# departure_board_display.net
KiCad netlist of a schematic drawn in EasyEDA Pro
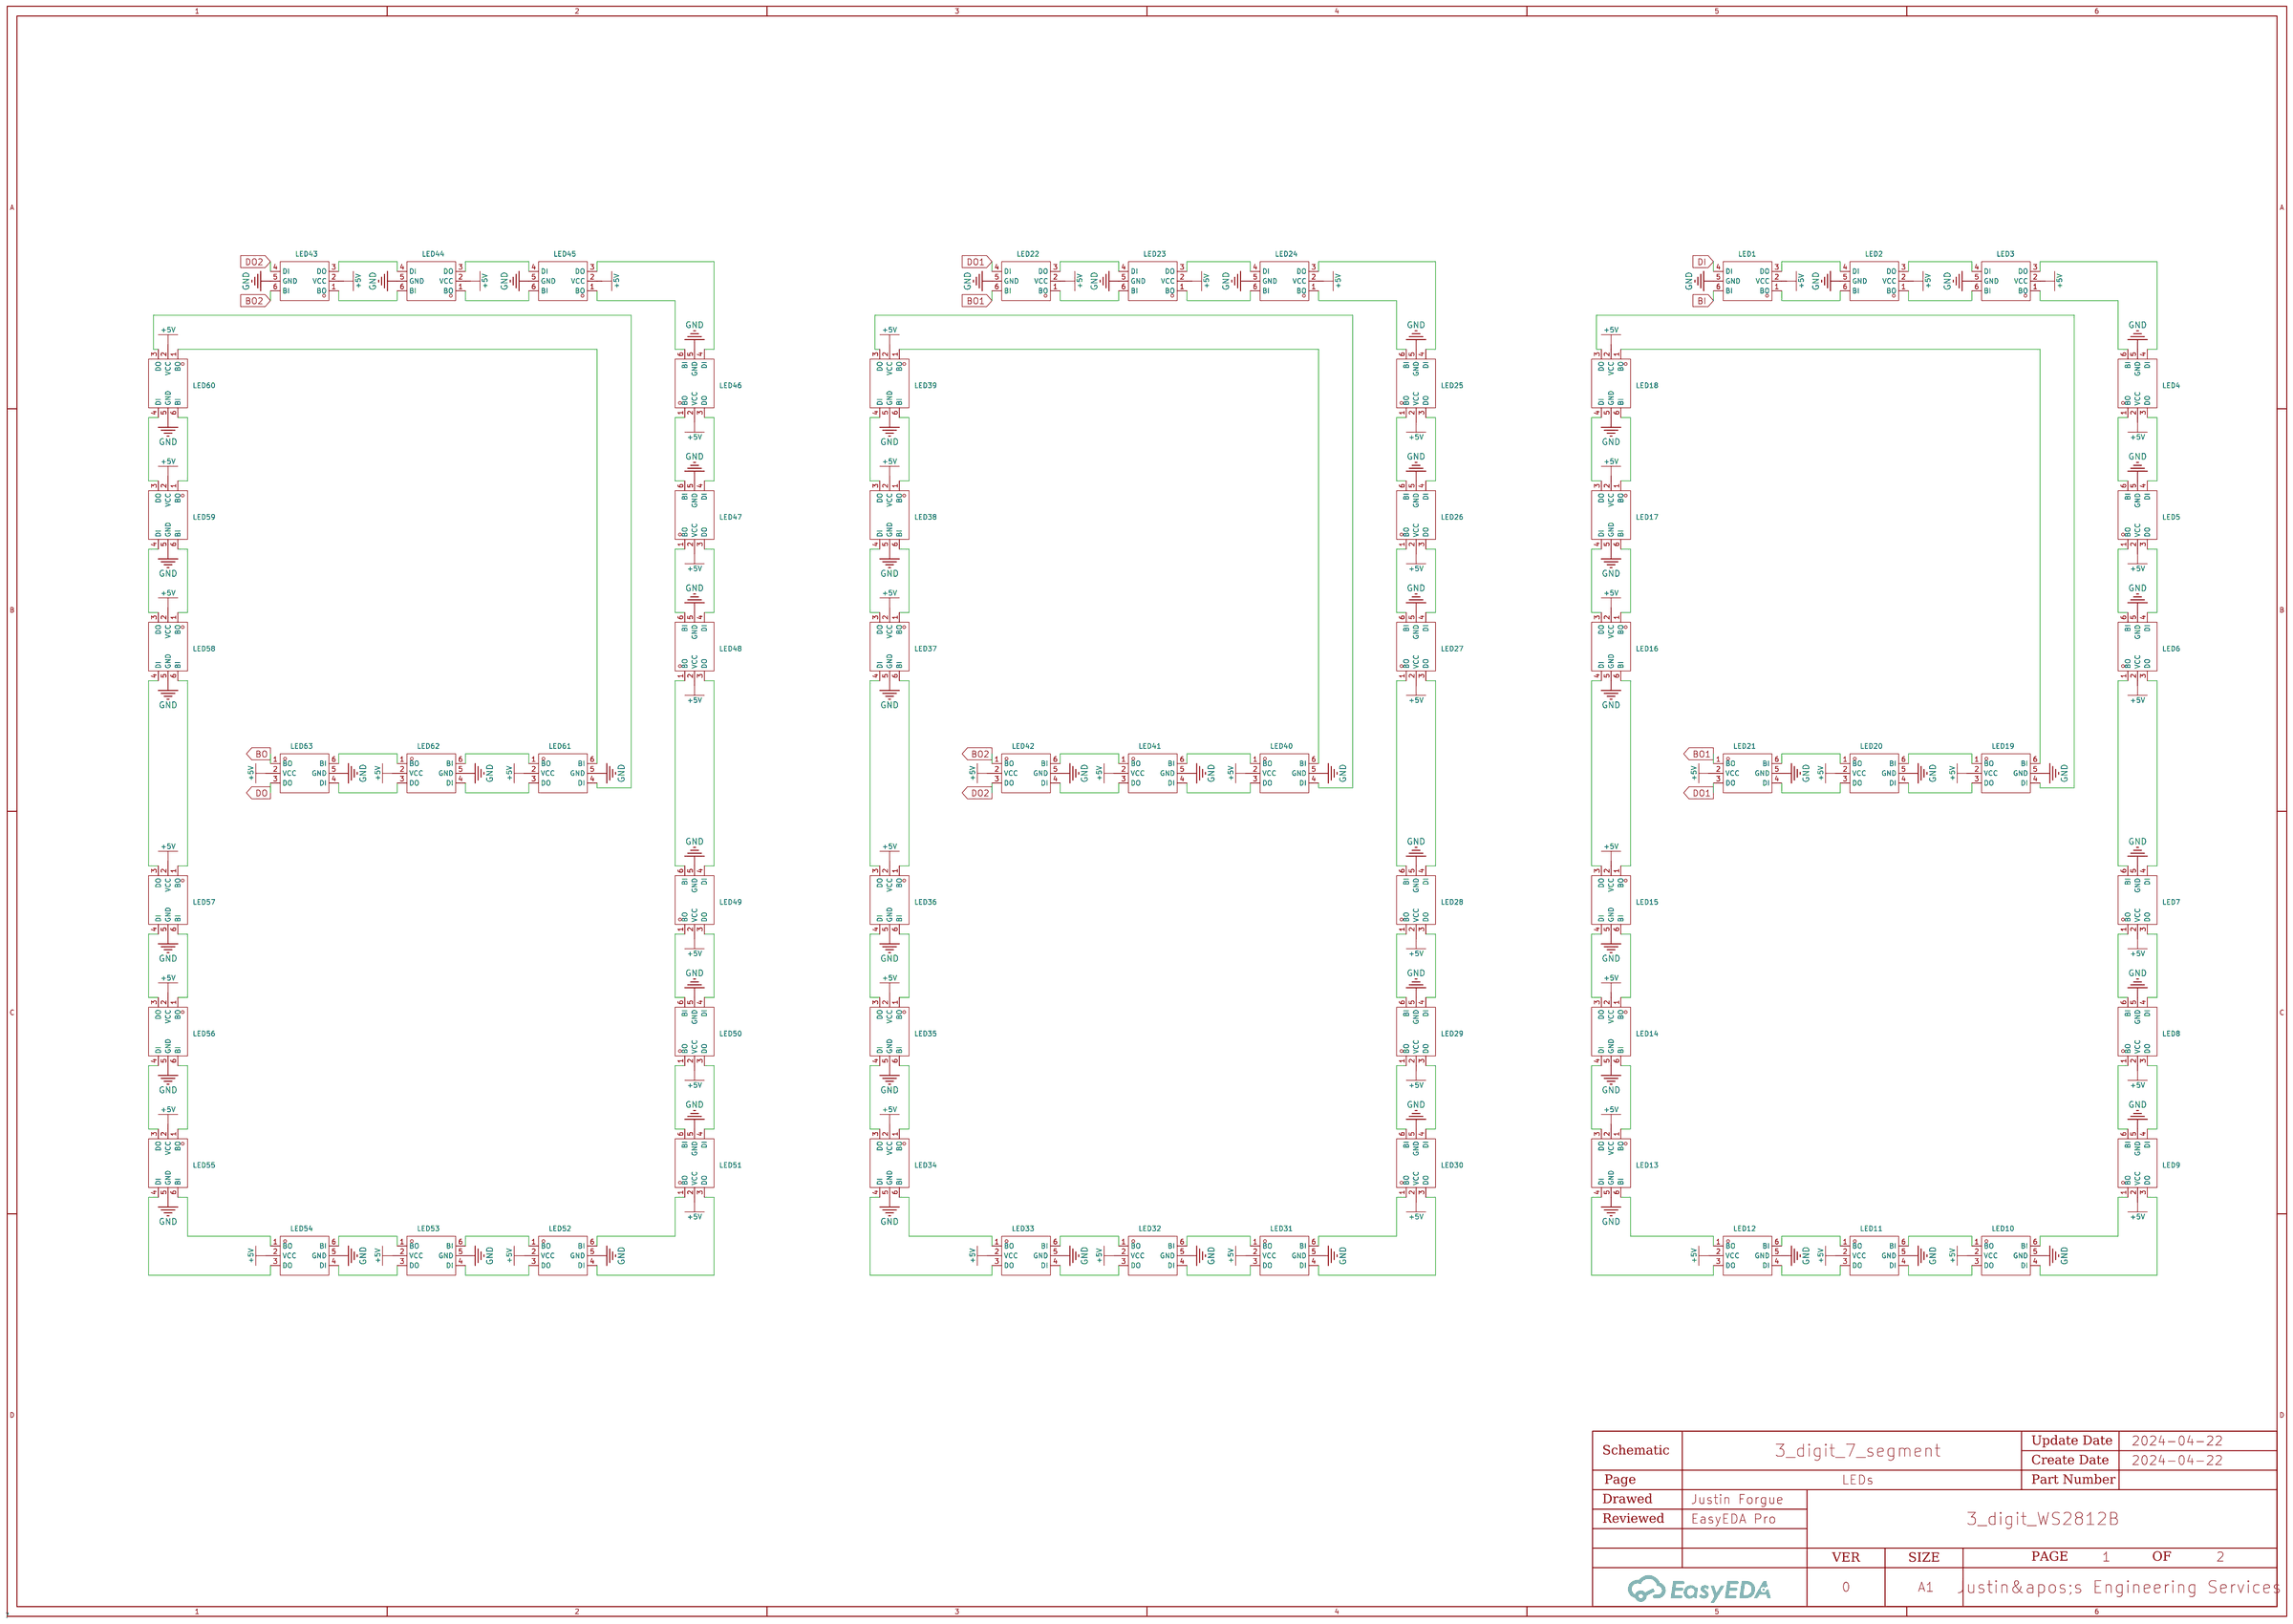
[diagram p0: LEDs]
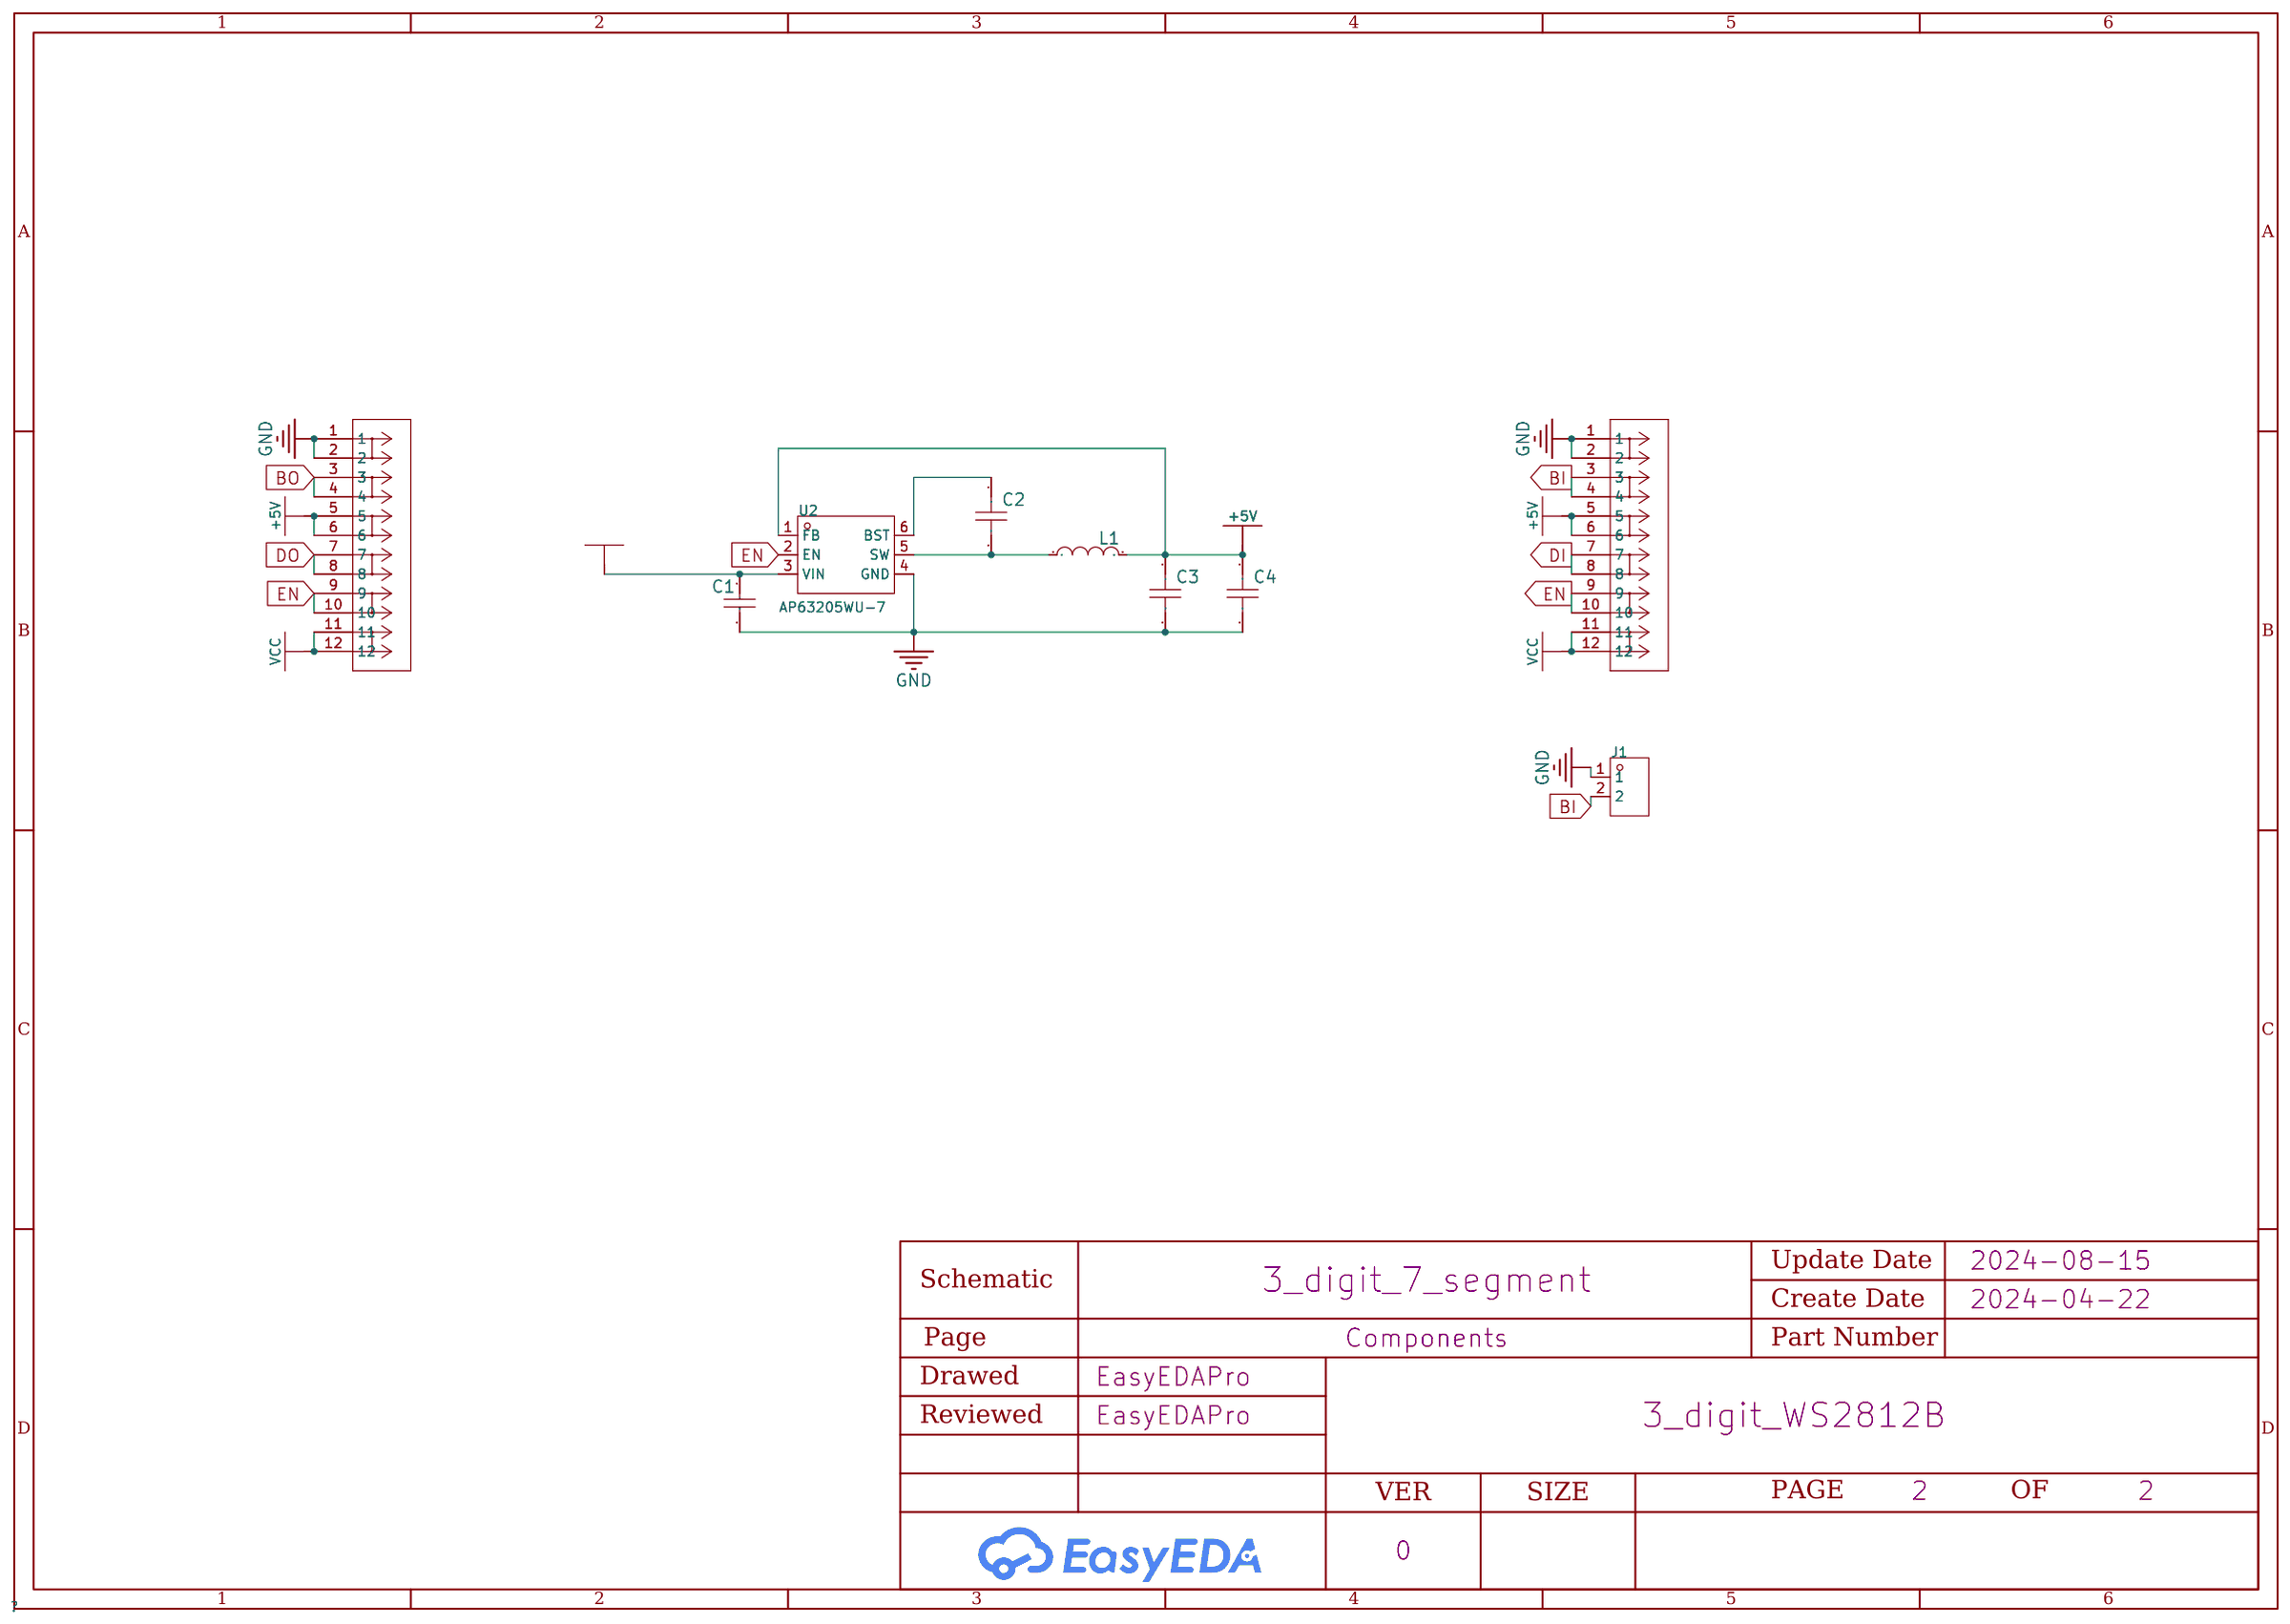
[diagram p1: Components]

(export (version "E")
  (design (tool "Eeschema 10.0.6"))
  (components
    (comp (ref "LED1")
      (value "WS2813B-V5")
      (footprint "easyedapro:LED-SMD_6P-L5.0-W5.0-TL")
      (fields (field (name "Manufacturer") "worldsemi"))
      (libsource (lib "easyedapro") (part "WS2813B-V5"))
    )
    (comp (ref "LED2")
      (value "WS2813B-V5")
      (footprint "easyedapro:LED-SMD_6P-L5.0-W5.0-TL")
      (fields (field (name "Manufacturer") "worldsemi"))
      (libsource (lib "easyedapro") (part "WS2813B-V5"))
    )
    (comp (ref "LED3")
      (value "WS2813B-V5")
      (footprint "easyedapro:LED-SMD_6P-L5.0-W5.0-TL")
      (fields (field (name "Manufacturer") "worldsemi"))
      (libsource (lib "easyedapro") (part "WS2813B-V5"))
    )
    (comp (ref "LED4")
      (value "WS2813B-V5")
      (footprint "easyedapro:LED-SMD_6P-L5.0-W5.0-TL")
      (fields (field (name "Manufacturer") "worldsemi"))
      (libsource (lib "easyedapro") (part "WS2813B-V5"))
    )
    (comp (ref "LED5")
      (value "WS2813B-V5")
      (footprint "easyedapro:LED-SMD_6P-L5.0-W5.0-TL")
      (fields (field (name "Manufacturer") "worldsemi"))
      (libsource (lib "easyedapro") (part "WS2813B-V5"))
    )
    (comp (ref "LED6")
      (value "WS2813B-V5")
      (footprint "easyedapro:LED-SMD_6P-L5.0-W5.0-TL")
      (fields (field (name "Manufacturer") "worldsemi"))
      (libsource (lib "easyedapro") (part "WS2813B-V5"))
    )
    (comp (ref "LED7")
      (value "WS2813B-V5")
      (footprint "easyedapro:LED-SMD_6P-L5.0-W5.0-TL")
      (fields (field (name "Manufacturer") "worldsemi"))
      (libsource (lib "easyedapro") (part "WS2813B-V5"))
    )
    (comp (ref "LED8")
      (value "WS2813B-V5")
      (footprint "easyedapro:LED-SMD_6P-L5.0-W5.0-TL")
      (fields (field (name "Manufacturer") "worldsemi"))
      (libsource (lib "easyedapro") (part "WS2813B-V5"))
    )
    (comp (ref "LED9")
      (value "WS2813B-V5")
      (footprint "easyedapro:LED-SMD_6P-L5.0-W5.0-TL")
      (fields (field (name "Manufacturer") "worldsemi"))
      (libsource (lib "easyedapro") (part "WS2813B-V5"))
    )
    (comp (ref "LED10")
      (value "WS2813B-V5")
      (footprint "easyedapro:LED-SMD_6P-L5.0-W5.0-TL")
      (fields (field (name "Manufacturer") "worldsemi"))
      (libsource (lib "easyedapro") (part "WS2813B-V5"))
    )
    (comp (ref "LED11")
      (value "WS2813B-V5")
      (footprint "easyedapro:LED-SMD_6P-L5.0-W5.0-TL")
      (fields (field (name "Manufacturer") "worldsemi"))
      (libsource (lib "easyedapro") (part "WS2813B-V5"))
    )
    (comp (ref "LED12")
      (value "WS2813B-V5")
      (footprint "easyedapro:LED-SMD_6P-L5.0-W5.0-TL")
      (fields (field (name "Manufacturer") "worldsemi"))
      (libsource (lib "easyedapro") (part "WS2813B-V5"))
    )
    (comp (ref "LED13")
      (value "WS2813B-V5")
      (footprint "easyedapro:LED-SMD_6P-L5.0-W5.0-TL")
      (fields (field (name "Manufacturer") "worldsemi"))
      (libsource (lib "easyedapro") (part "WS2813B-V5"))
    )
    (comp (ref "LED14")
      (value "WS2813B-V5")
      (footprint "easyedapro:LED-SMD_6P-L5.0-W5.0-TL")
      (fields (field (name "Manufacturer") "worldsemi"))
      (libsource (lib "easyedapro") (part "WS2813B-V5"))
    )
    (comp (ref "LED15")
      (value "WS2813B-V5")
      (footprint "easyedapro:LED-SMD_6P-L5.0-W5.0-TL")
      (fields (field (name "Manufacturer") "worldsemi"))
      (libsource (lib "easyedapro") (part "WS2813B-V5"))
    )
    (comp (ref "LED16")
      (value "WS2813B-V5")
      (footprint "easyedapro:LED-SMD_6P-L5.0-W5.0-TL")
      (fields (field (name "Manufacturer") "worldsemi"))
      (libsource (lib "easyedapro") (part "WS2813B-V5"))
    )
    (comp (ref "LED17")
      (value "WS2813B-V5")
      (footprint "easyedapro:LED-SMD_6P-L5.0-W5.0-TL")
      (fields (field (name "Manufacturer") "worldsemi"))
      (libsource (lib "easyedapro") (part "WS2813B-V5"))
    )
    (comp (ref "LED18")
      (value "WS2813B-V5")
      (footprint "easyedapro:LED-SMD_6P-L5.0-W5.0-TL")
      (fields (field (name "Manufacturer") "worldsemi"))
      (libsource (lib "easyedapro") (part "WS2813B-V5"))
    )
    (comp (ref "LED19")
      (value "WS2813B-V5")
      (footprint "easyedapro:LED-SMD_6P-L5.0-W5.0-TL")
      (fields (field (name "Manufacturer") "worldsemi"))
      (libsource (lib "easyedapro") (part "WS2813B-V5"))
    )
    (comp (ref "LED20")
      (value "WS2813B-V5")
      (footprint "easyedapro:LED-SMD_6P-L5.0-W5.0-TL")
      (fields (field (name "Manufacturer") "worldsemi"))
      (libsource (lib "easyedapro") (part "WS2813B-V5"))
    )
    (comp (ref "LED21")
      (value "WS2813B-V5")
      (footprint "easyedapro:LED-SMD_6P-L5.0-W5.0-TL")
      (fields (field (name "Manufacturer") "worldsemi"))
      (libsource (lib "easyedapro") (part "WS2813B-V5"))
    )
    (comp (ref "LED22")
      (value "WS2813B-V5")
      (footprint "easyedapro:LED-SMD_6P-L5.0-W5.0-TL")
      (fields (field (name "Manufacturer") "worldsemi"))
      (libsource (lib "easyedapro") (part "WS2813B-V5"))
    )
    (comp (ref "LED23")
      (value "WS2813B-V5")
      (footprint "easyedapro:LED-SMD_6P-L5.0-W5.0-TL")
      (fields (field (name "Manufacturer") "worldsemi"))
      (libsource (lib "easyedapro") (part "WS2813B-V5"))
    )
    (comp (ref "LED24")
      (value "WS2813B-V5")
      (footprint "easyedapro:LED-SMD_6P-L5.0-W5.0-TL")
      (fields (field (name "Manufacturer") "worldsemi"))
      (libsource (lib "easyedapro") (part "WS2813B-V5"))
    )
    (comp (ref "LED25")
      (value "WS2813B-V5")
      (footprint "easyedapro:LED-SMD_6P-L5.0-W5.0-TL")
      (fields (field (name "Manufacturer") "worldsemi"))
      (libsource (lib "easyedapro") (part "WS2813B-V5"))
    )
    (comp (ref "LED26")
      (value "WS2813B-V5")
      (footprint "easyedapro:LED-SMD_6P-L5.0-W5.0-TL")
      (fields (field (name "Manufacturer") "worldsemi"))
      (libsource (lib "easyedapro") (part "WS2813B-V5"))
    )
    (comp (ref "LED27")
      (value "WS2813B-V5")
      (footprint "easyedapro:LED-SMD_6P-L5.0-W5.0-TL")
      (fields (field (name "Manufacturer") "worldsemi"))
      (libsource (lib "easyedapro") (part "WS2813B-V5"))
    )
    (comp (ref "LED28")
      (value "WS2813B-V5")
      (footprint "easyedapro:LED-SMD_6P-L5.0-W5.0-TL")
      (fields (field (name "Manufacturer") "worldsemi"))
      (libsource (lib "easyedapro") (part "WS2813B-V5"))
    )
    (comp (ref "LED29")
      (value "WS2813B-V5")
      (footprint "easyedapro:LED-SMD_6P-L5.0-W5.0-TL")
      (fields (field (name "Manufacturer") "worldsemi"))
      (libsource (lib "easyedapro") (part "WS2813B-V5"))
    )
    (comp (ref "LED30")
      (value "WS2813B-V5")
      (footprint "easyedapro:LED-SMD_6P-L5.0-W5.0-TL")
      (fields (field (name "Manufacturer") "worldsemi"))
      (libsource (lib "easyedapro") (part "WS2813B-V5"))
    )
    (comp (ref "LED31")
      (value "WS2813B-V5")
      (footprint "easyedapro:LED-SMD_6P-L5.0-W5.0-TL")
      (fields (field (name "Manufacturer") "worldsemi"))
      (libsource (lib "easyedapro") (part "WS2813B-V5"))
    )
    (comp (ref "LED32")
      (value "WS2813B-V5")
      (footprint "easyedapro:LED-SMD_6P-L5.0-W5.0-TL")
      (fields (field (name "Manufacturer") "worldsemi"))
      (libsource (lib "easyedapro") (part "WS2813B-V5"))
    )
    (comp (ref "LED33")
      (value "WS2813B-V5")
      (footprint "easyedapro:LED-SMD_6P-L5.0-W5.0-TL")
      (fields (field (name "Manufacturer") "worldsemi"))
      (libsource (lib "easyedapro") (part "WS2813B-V5"))
    )
    (comp (ref "LED34")
      (value "WS2813B-V5")
      (footprint "easyedapro:LED-SMD_6P-L5.0-W5.0-TL")
      (fields (field (name "Manufacturer") "worldsemi"))
      (libsource (lib "easyedapro") (part "WS2813B-V5"))
    )
    (comp (ref "LED35")
      (value "WS2813B-V5")
      (footprint "easyedapro:LED-SMD_6P-L5.0-W5.0-TL")
      (fields (field (name "Manufacturer") "worldsemi"))
      (libsource (lib "easyedapro") (part "WS2813B-V5"))
    )
    (comp (ref "LED36")
      (value "WS2813B-V5")
      (footprint "easyedapro:LED-SMD_6P-L5.0-W5.0-TL")
      (fields (field (name "Manufacturer") "worldsemi"))
      (libsource (lib "easyedapro") (part "WS2813B-V5"))
    )
    (comp (ref "LED37")
      (value "WS2813B-V5")
      (footprint "easyedapro:LED-SMD_6P-L5.0-W5.0-TL")
      (fields (field (name "Manufacturer") "worldsemi"))
      (libsource (lib "easyedapro") (part "WS2813B-V5"))
    )
    (comp (ref "LED38")
      (value "WS2813B-V5")
      (footprint "easyedapro:LED-SMD_6P-L5.0-W5.0-TL")
      (fields (field (name "Manufacturer") "worldsemi"))
      (libsource (lib "easyedapro") (part "WS2813B-V5"))
    )
    (comp (ref "LED39")
      (value "WS2813B-V5")
      (footprint "easyedapro:LED-SMD_6P-L5.0-W5.0-TL")
      (fields (field (name "Manufacturer") "worldsemi"))
      (libsource (lib "easyedapro") (part "WS2813B-V5"))
    )
    (comp (ref "LED40")
      (value "WS2813B-V5")
      (footprint "easyedapro:LED-SMD_6P-L5.0-W5.0-TL")
      (fields (field (name "Manufacturer") "worldsemi"))
      (libsource (lib "easyedapro") (part "WS2813B-V5"))
    )
    (comp (ref "LED41")
      (value "WS2813B-V5")
      (footprint "easyedapro:LED-SMD_6P-L5.0-W5.0-TL")
      (fields (field (name "Manufacturer") "worldsemi"))
      (libsource (lib "easyedapro") (part "WS2813B-V5"))
    )
    (comp (ref "LED42")
      (value "WS2813B-V5")
      (footprint "easyedapro:LED-SMD_6P-L5.0-W5.0-TL")
      (fields (field (name "Manufacturer") "worldsemi"))
      (libsource (lib "easyedapro") (part "WS2813B-V5"))
    )
    (comp (ref "LED43")
      (value "WS2813B-V5")
      (footprint "easyedapro:LED-SMD_6P-L5.0-W5.0-TL")
      (fields (field (name "Manufacturer") "worldsemi"))
      (libsource (lib "easyedapro") (part "WS2813B-V5"))
    )
    (comp (ref "LED44")
      (value "WS2813B-V5")
      (footprint "easyedapro:LED-SMD_6P-L5.0-W5.0-TL")
      (fields (field (name "Manufacturer") "worldsemi"))
      (libsource (lib "easyedapro") (part "WS2813B-V5"))
    )
    (comp (ref "LED45")
      (value "WS2813B-V5")
      (footprint "easyedapro:LED-SMD_6P-L5.0-W5.0-TL")
      (fields (field (name "Manufacturer") "worldsemi"))
      (libsource (lib "easyedapro") (part "WS2813B-V5"))
    )
    (comp (ref "LED46")
      (value "WS2813B-V5")
      (footprint "easyedapro:LED-SMD_6P-L5.0-W5.0-TL")
      (fields (field (name "Manufacturer") "worldsemi"))
      (libsource (lib "easyedapro") (part "WS2813B-V5"))
    )
    (comp (ref "LED47")
      (value "WS2813B-V5")
      (footprint "easyedapro:LED-SMD_6P-L5.0-W5.0-TL")
      (fields (field (name "Manufacturer") "worldsemi"))
      (libsource (lib "easyedapro") (part "WS2813B-V5"))
    )
    (comp (ref "LED48")
      (value "WS2813B-V5")
      (footprint "easyedapro:LED-SMD_6P-L5.0-W5.0-TL")
      (fields (field (name "Manufacturer") "worldsemi"))
      (libsource (lib "easyedapro") (part "WS2813B-V5"))
    )
    (comp (ref "LED49")
      (value "WS2813B-V5")
      (footprint "easyedapro:LED-SMD_6P-L5.0-W5.0-TL")
      (fields (field (name "Manufacturer") "worldsemi"))
      (libsource (lib "easyedapro") (part "WS2813B-V5"))
    )
    (comp (ref "LED50")
      (value "WS2813B-V5")
      (footprint "easyedapro:LED-SMD_6P-L5.0-W5.0-TL")
      (fields (field (name "Manufacturer") "worldsemi"))
      (libsource (lib "easyedapro") (part "WS2813B-V5"))
    )
    (comp (ref "LED51")
      (value "WS2813B-V5")
      (footprint "easyedapro:LED-SMD_6P-L5.0-W5.0-TL")
      (fields (field (name "Manufacturer") "worldsemi"))
      (libsource (lib "easyedapro") (part "WS2813B-V5"))
    )
    (comp (ref "LED52")
      (value "WS2813B-V5")
      (footprint "easyedapro:LED-SMD_6P-L5.0-W5.0-TL")
      (fields (field (name "Manufacturer") "worldsemi"))
      (libsource (lib "easyedapro") (part "WS2813B-V5"))
    )
    (comp (ref "LED53")
      (value "WS2813B-V5")
      (footprint "easyedapro:LED-SMD_6P-L5.0-W5.0-TL")
      (fields (field (name "Manufacturer") "worldsemi"))
      (libsource (lib "easyedapro") (part "WS2813B-V5"))
    )
    (comp (ref "LED54")
      (value "WS2813B-V5")
      (footprint "easyedapro:LED-SMD_6P-L5.0-W5.0-TL")
      (fields (field (name "Manufacturer") "worldsemi"))
      (libsource (lib "easyedapro") (part "WS2813B-V5"))
    )
    (comp (ref "LED55")
      (value "WS2813B-V5")
      (footprint "easyedapro:LED-SMD_6P-L5.0-W5.0-TL")
      (fields (field (name "Manufacturer") "worldsemi"))
      (libsource (lib "easyedapro") (part "WS2813B-V5"))
    )
    (comp (ref "LED56")
      (value "WS2813B-V5")
      (footprint "easyedapro:LED-SMD_6P-L5.0-W5.0-TL")
      (fields (field (name "Manufacturer") "worldsemi"))
      (libsource (lib "easyedapro") (part "WS2813B-V5"))
    )
    (comp (ref "LED57")
      (value "WS2813B-V5")
      (footprint "easyedapro:LED-SMD_6P-L5.0-W5.0-TL")
      (fields (field (name "Manufacturer") "worldsemi"))
      (libsource (lib "easyedapro") (part "WS2813B-V5"))
    )
    (comp (ref "LED58")
      (value "WS2813B-V5")
      (footprint "easyedapro:LED-SMD_6P-L5.0-W5.0-TL")
      (fields (field (name "Manufacturer") "worldsemi"))
      (libsource (lib "easyedapro") (part "WS2813B-V5"))
    )
    (comp (ref "LED59")
      (value "WS2813B-V5")
      (footprint "easyedapro:LED-SMD_6P-L5.0-W5.0-TL")
      (fields (field (name "Manufacturer") "worldsemi"))
      (libsource (lib "easyedapro") (part "WS2813B-V5"))
    )
    (comp (ref "LED60")
      (value "WS2813B-V5")
      (footprint "easyedapro:LED-SMD_6P-L5.0-W5.0-TL")
      (fields (field (name "Manufacturer") "worldsemi"))
      (libsource (lib "easyedapro") (part "WS2813B-V5"))
    )
    (comp (ref "LED61")
      (value "WS2813B-V5")
      (footprint "easyedapro:LED-SMD_6P-L5.0-W5.0-TL")
      (fields (field (name "Manufacturer") "worldsemi"))
      (libsource (lib "easyedapro") (part "WS2813B-V5"))
    )
    (comp (ref "LED62")
      (value "WS2813B-V5")
      (footprint "easyedapro:LED-SMD_6P-L5.0-W5.0-TL")
      (fields (field (name "Manufacturer") "worldsemi"))
      (libsource (lib "easyedapro") (part "WS2813B-V5"))
    )
    (comp (ref "LED63")
      (value "WS2813B-V5")
      (footprint "easyedapro:LED-SMD_6P-L5.0-W5.0-TL")
      (fields (field (name "Manufacturer") "worldsemi"))
      (libsource (lib "easyedapro") (part "WS2813B-V5"))
    )
    (comp (ref "C1")
      (value "10uF")
      (footprint "easyedapro:C1210")
      (fields
        (field (name "Manufacturer Part") "CL32B106KAJNNNE")
        (field (name "Manufacturer") "SAMSUNG(三星)")
      )
      (libsource (lib "easyedapro") (part "CL32B106KAJNNNE"))
    )
    (comp (ref "C2")
      (value "100nF")
      (footprint "easyedapro:C1206")
      (fields (field (name "Manufacturer Part") "1206N104J500CT") (field (name "Manufacturer") "Walsin(华新科)"))
      (libsource (lib "easyedapro") (part "1206N104J500"))
    )
    (comp (ref "C3")
      (value "22uF")
      (footprint "easyedapro:C1210")
      (fields
        (field (name "Manufacturer Part") "CL32B226KAJNNNE")
        (field (name "Manufacturer") "SAMSUNG(三星)")
      )
      (libsource (lib "easyedapro") (part "CL32B226KAJNNNE"))
    )
    (comp (ref "C4")
      (value "22uF")
      (footprint "easyedapro:C1210")
      (fields
        (field (name "Manufacturer Part") "CL32B226KAJNNNE")
        (field (name "Manufacturer") "SAMSUNG(三星)")
      )
      (libsource (lib "easyedapro") (part "CL32B226KAJNNNE"))
    )
    (comp (ref "H1")
      (value "~")
      (footprint "easyedapro:CONN_1814605")
      (description "TERM BLK 6P TOP ENTRY 2.5MM PCB")
      (libsource (lib "easyedapro") (part "1770995"))
    )
    (comp (ref "H2")
      (value "~")
      (footprint "easyedapro:CONN_1814605")
      (description "TERM BLK 6P TOP ENTRY 2.5MM PCB")
      (libsource (lib "easyedapro") (part "1770995"))
    )
    (comp (ref "J1")
      (value "PZ254V-11-02P")
      (footprint "easyedapro:HDR-TH_2P-P2.54-V-M")
      (fields (field (name "Manufacturer") "XFCN(兴飞)"))
      (libsource (lib "easyedapro") (part "PZ254V-11-02P"))
    )
    (comp (ref "L1")
      (value "4.7uH")
      (footprint "easyedapro:IND-SMD_L3.2-W2.5_CMI3225XX")
      (fields
        (field (name "Manufacturer Part") "DFE322520FD-4R7M=P2")
        (field (name "Manufacturer") "muRata(村田)")
      )
      (libsource (lib "easyedapro") (part "DFE322520FD-4R7M=P2"))
    )
    (comp (ref "U2")
      (value "AP63205WU-7")
      (footprint "easyedapro:TSOT-23-6_L2.9-W1.6-P0.95-LS2.8-BL")
      (fields (field (name "Manufacturer") "DIODES(美台)"))
      (libsource (lib "easyedapro") (part "AP63205WU-7"))
    )
  )
  (nets
    (net (code "1") (name "+5V") (class "Default")
      (node (ref "C3") (pin "1") (pinfunction "1_1") (pintype "unspecified"))
      (node (ref "C4") (pin "1") (pinfunction "1_1") (pintype "unspecified"))
      (node (ref "H1") (pin "5") (pinfunction "5_5") (pintype "unspecified"))
      (node (ref "H1") (pin "6") (pinfunction "6_6") (pintype "unspecified"))
      (node (ref "H2") (pin "5") (pinfunction "5_5") (pintype "unspecified"))
      (node (ref "H2") (pin "6") (pinfunction "6_6") (pintype "unspecified"))
      (node (ref "L1") (pin "2") (pinfunction "2_2") (pintype "unspecified"))
      (node (ref "LED1") (pin "2") (pinfunction "VCC_2") (pintype "input"))
      (node (ref "LED10") (pin "2") (pinfunction "VCC_2") (pintype "input"))
      (node (ref "LED11") (pin "2") (pinfunction "VCC_2") (pintype "input"))
      (node (ref "LED12") (pin "2") (pinfunction "VCC_2") (pintype "input"))
      (node (ref "LED13") (pin "2") (pinfunction "VCC_2") (pintype "input"))
      (node (ref "LED14") (pin "2") (pinfunction "VCC_2") (pintype "input"))
      (node (ref "LED15") (pin "2") (pinfunction "VCC_2") (pintype "input"))
      (node (ref "LED16") (pin "2") (pinfunction "VCC_2") (pintype "input"))
      (node (ref "LED17") (pin "2") (pinfunction "VCC_2") (pintype "input"))
      (node (ref "LED18") (pin "2") (pinfunction "VCC_2") (pintype "input"))
      (node (ref "LED19") (pin "2") (pinfunction "VCC_2") (pintype "input"))
      (node (ref "LED2") (pin "2") (pinfunction "VCC_2") (pintype "input"))
      (node (ref "LED20") (pin "2") (pinfunction "VCC_2") (pintype "input"))
      (node (ref "LED21") (pin "2") (pinfunction "VCC_2") (pintype "input"))
      (node (ref "LED22") (pin "2") (pinfunction "VCC_2") (pintype "input"))
      (node (ref "LED23") (pin "2") (pinfunction "VCC_2") (pintype "input"))
      (node (ref "LED24") (pin "2") (pinfunction "VCC_2") (pintype "input"))
      (node (ref "LED25") (pin "2") (pinfunction "VCC_2") (pintype "input"))
      (node (ref "LED26") (pin "2") (pinfunction "VCC_2") (pintype "input"))
      (node (ref "LED27") (pin "2") (pinfunction "VCC_2") (pintype "input"))
      (node (ref "LED28") (pin "2") (pinfunction "VCC_2") (pintype "input"))
      (node (ref "LED29") (pin "2") (pinfunction "VCC_2") (pintype "input"))
      (node (ref "LED3") (pin "2") (pinfunction "VCC_2") (pintype "input"))
      (node (ref "LED30") (pin "2") (pinfunction "VCC_2") (pintype "input"))
      (node (ref "LED31") (pin "2") (pinfunction "VCC_2") (pintype "input"))
      (node (ref "LED32") (pin "2") (pinfunction "VCC_2") (pintype "input"))
      (node (ref "LED33") (pin "2") (pinfunction "VCC_2") (pintype "input"))
      (node (ref "LED34") (pin "2") (pinfunction "VCC_2") (pintype "input"))
      (node (ref "LED35") (pin "2") (pinfunction "VCC_2") (pintype "input"))
      (node (ref "LED36") (pin "2") (pinfunction "VCC_2") (pintype "input"))
      (node (ref "LED37") (pin "2") (pinfunction "VCC_2") (pintype "input"))
      (node (ref "LED38") (pin "2") (pinfunction "VCC_2") (pintype "input"))
      (node (ref "LED39") (pin "2") (pinfunction "VCC_2") (pintype "input"))
      (node (ref "LED4") (pin "2") (pinfunction "VCC_2") (pintype "input"))
      (node (ref "LED40") (pin "2") (pinfunction "VCC_2") (pintype "input"))
      (node (ref "LED41") (pin "2") (pinfunction "VCC_2") (pintype "input"))
      (node (ref "LED42") (pin "2") (pinfunction "VCC_2") (pintype "input"))
      (node (ref "LED43") (pin "2") (pinfunction "VCC_2") (pintype "input"))
      (node (ref "LED44") (pin "2") (pinfunction "VCC_2") (pintype "input"))
      (node (ref "LED45") (pin "2") (pinfunction "VCC_2") (pintype "input"))
      (node (ref "LED46") (pin "2") (pinfunction "VCC_2") (pintype "input"))
      (node (ref "LED47") (pin "2") (pinfunction "VCC_2") (pintype "input"))
      (node (ref "LED48") (pin "2") (pinfunction "VCC_2") (pintype "input"))
      (node (ref "LED49") (pin "2") (pinfunction "VCC_2") (pintype "input"))
      (node (ref "LED5") (pin "2") (pinfunction "VCC_2") (pintype "input"))
      (node (ref "LED50") (pin "2") (pinfunction "VCC_2") (pintype "input"))
      (node (ref "LED51") (pin "2") (pinfunction "VCC_2") (pintype "input"))
      (node (ref "LED52") (pin "2") (pinfunction "VCC_2") (pintype "input"))
      (node (ref "LED53") (pin "2") (pinfunction "VCC_2") (pintype "input"))
      (node (ref "LED54") (pin "2") (pinfunction "VCC_2") (pintype "input"))
      (node (ref "LED55") (pin "2") (pinfunction "VCC_2") (pintype "input"))
      (node (ref "LED56") (pin "2") (pinfunction "VCC_2") (pintype "input"))
      (node (ref "LED57") (pin "2") (pinfunction "VCC_2") (pintype "input"))
      (node (ref "LED58") (pin "2") (pinfunction "VCC_2") (pintype "input"))
      (node (ref "LED59") (pin "2") (pinfunction "VCC_2") (pintype "input"))
      (node (ref "LED6") (pin "2") (pinfunction "VCC_2") (pintype "input"))
      (node (ref "LED60") (pin "2") (pinfunction "VCC_2") (pintype "input"))
      (node (ref "LED61") (pin "2") (pinfunction "VCC_2") (pintype "input"))
      (node (ref "LED62") (pin "2") (pinfunction "VCC_2") (pintype "input"))
      (node (ref "LED63") (pin "2") (pinfunction "VCC_2") (pintype "input"))
      (node (ref "LED7") (pin "2") (pinfunction "VCC_2") (pintype "input"))
      (node (ref "LED8") (pin "2") (pinfunction "VCC_2") (pintype "input"))
      (node (ref "LED9") (pin "2") (pinfunction "VCC_2") (pintype "input"))
      (node (ref "U2") (pin "1") (pinfunction "FB_1") (pintype "input"))
    )
    (net (code "2") (name "BI") (class "Default")
      (node (ref "H1") (pin "3") (pinfunction "3_3") (pintype "unspecified"))
      (node (ref "H1") (pin "4") (pinfunction "4_4") (pintype "unspecified"))
      (node (ref "J1") (pin "2") (pinfunction "2_2") (pintype "input"))
      (node (ref "LED1") (pin "6") (pinfunction "BI_6") (pintype "input"))
    )
    (net (code "3") (name "BO") (class "Default")
      (node (ref "H2") (pin "3") (pinfunction "3_3") (pintype "unspecified"))
      (node (ref "H2") (pin "4") (pinfunction "4_4") (pintype "unspecified"))
      (node (ref "LED63") (pin "1") (pinfunction "BO_1") (pintype "input"))
    )
    (net (code "4") (name "BO1") (class "Default")
      (node (ref "LED21") (pin "1") (pinfunction "BO_1") (pintype "input"))
      (node (ref "LED22") (pin "6") (pinfunction "BI_6") (pintype "input"))
    )
    (net (code "5") (name "BO2") (class "Default")
      (node (ref "LED42") (pin "1") (pinfunction "BO_1") (pintype "input"))
      (node (ref "LED43") (pin "6") (pinfunction "BI_6") (pintype "input"))
    )
    (net (code "6") (name "DI") (class "Default")
      (node (ref "H1") (pin "7") (pinfunction "7_7") (pintype "unspecified"))
      (node (ref "H1") (pin "8") (pinfunction "8_8") (pintype "unspecified"))
      (node (ref "LED1") (pin "4") (pinfunction "DI_4") (pintype "input"))
    )
    (net (code "7") (name "DO") (class "Default")
      (node (ref "H2") (pin "7") (pinfunction "7_7") (pintype "unspecified"))
      (node (ref "H2") (pin "8") (pinfunction "8_8") (pintype "unspecified"))
      (node (ref "LED63") (pin "3") (pinfunction "DO_3") (pintype "input"))
    )
    (net (code "8") (name "DO1") (class "Default")
      (node (ref "LED21") (pin "3") (pinfunction "DO_3") (pintype "input"))
      (node (ref "LED22") (pin "4") (pinfunction "DI_4") (pintype "input"))
    )
    (net (code "9") (name "DO2") (class "Default")
      (node (ref "LED42") (pin "3") (pinfunction "DO_3") (pintype "input"))
      (node (ref "LED43") (pin "4") (pinfunction "DI_4") (pintype "input"))
    )
    (net (code "10") (name "EN") (class "Default")
      (node (ref "H1") (pin "10") (pinfunction "10_10") (pintype "unspecified"))
      (node (ref "H1") (pin "9") (pinfunction "9_9") (pintype "unspecified"))
      (node (ref "H2") (pin "10") (pinfunction "10_10") (pintype "unspecified"))
      (node (ref "H2") (pin "9") (pinfunction "9_9") (pintype "unspecified"))
      (node (ref "U2") (pin "2") (pinfunction "EN_2") (pintype "input"))
    )
    (net (code "11") (name "GND") (class "Default")
      (node (ref "C1") (pin "2") (pinfunction "2_2") (pintype "input"))
      (node (ref "C3") (pin "2") (pinfunction "2_2") (pintype "unspecified"))
      (node (ref "C4") (pin "2") (pinfunction "2_2") (pintype "unspecified"))
      (node (ref "H1") (pin "1") (pinfunction "1_1") (pintype "unspecified"))
      (node (ref "H1") (pin "2") (pinfunction "2_2") (pintype "unspecified"))
      (node (ref "H2") (pin "1") (pinfunction "1_1") (pintype "unspecified"))
      (node (ref "H2") (pin "2") (pinfunction "2_2") (pintype "unspecified"))
      (node (ref "J1") (pin "1") (pinfunction "1_1") (pintype "input"))
      (node (ref "LED1") (pin "5") (pinfunction "GND_5") (pintype "input"))
      (node (ref "LED10") (pin "5") (pinfunction "GND_5") (pintype "input"))
      (node (ref "LED11") (pin "5") (pinfunction "GND_5") (pintype "input"))
      (node (ref "LED12") (pin "5") (pinfunction "GND_5") (pintype "input"))
      (node (ref "LED13") (pin "5") (pinfunction "GND_5") (pintype "input"))
      (node (ref "LED14") (pin "5") (pinfunction "GND_5") (pintype "input"))
      (node (ref "LED15") (pin "5") (pinfunction "GND_5") (pintype "input"))
      (node (ref "LED16") (pin "5") (pinfunction "GND_5") (pintype "input"))
      (node (ref "LED17") (pin "5") (pinfunction "GND_5") (pintype "input"))
      (node (ref "LED18") (pin "5") (pinfunction "GND_5") (pintype "input"))
      (node (ref "LED19") (pin "5") (pinfunction "GND_5") (pintype "input"))
      (node (ref "LED2") (pin "5") (pinfunction "GND_5") (pintype "input"))
      (node (ref "LED20") (pin "5") (pinfunction "GND_5") (pintype "input"))
      (node (ref "LED21") (pin "5") (pinfunction "GND_5") (pintype "input"))
      (node (ref "LED22") (pin "5") (pinfunction "GND_5") (pintype "input"))
      (node (ref "LED23") (pin "5") (pinfunction "GND_5") (pintype "input"))
      (node (ref "LED24") (pin "5") (pinfunction "GND_5") (pintype "input"))
      (node (ref "LED25") (pin "5") (pinfunction "GND_5") (pintype "input"))
      (node (ref "LED26") (pin "5") (pinfunction "GND_5") (pintype "input"))
      (node (ref "LED27") (pin "5") (pinfunction "GND_5") (pintype "input"))
      (node (ref "LED28") (pin "5") (pinfunction "GND_5") (pintype "input"))
      (node (ref "LED29") (pin "5") (pinfunction "GND_5") (pintype "input"))
      (node (ref "LED3") (pin "5") (pinfunction "GND_5") (pintype "input"))
      (node (ref "LED30") (pin "5") (pinfunction "GND_5") (pintype "input"))
      (node (ref "LED31") (pin "5") (pinfunction "GND_5") (pintype "input"))
      (node (ref "LED32") (pin "5") (pinfunction "GND_5") (pintype "input"))
      (node (ref "LED33") (pin "5") (pinfunction "GND_5") (pintype "input"))
      (node (ref "LED34") (pin "5") (pinfunction "GND_5") (pintype "input"))
      (node (ref "LED35") (pin "5") (pinfunction "GND_5") (pintype "input"))
      (node (ref "LED36") (pin "5") (pinfunction "GND_5") (pintype "input"))
      (node (ref "LED37") (pin "5") (pinfunction "GND_5") (pintype "input"))
      (node (ref "LED38") (pin "5") (pinfunction "GND_5") (pintype "input"))
      (node (ref "LED39") (pin "5") (pinfunction "GND_5") (pintype "input"))
      (node (ref "LED4") (pin "5") (pinfunction "GND_5") (pintype "input"))
      (node (ref "LED40") (pin "5") (pinfunction "GND_5") (pintype "input"))
      (node (ref "LED41") (pin "5") (pinfunction "GND_5") (pintype "input"))
      (node (ref "LED42") (pin "5") (pinfunction "GND_5") (pintype "input"))
      (node (ref "LED43") (pin "5") (pinfunction "GND_5") (pintype "input"))
      (node (ref "LED44") (pin "5") (pinfunction "GND_5") (pintype "input"))
      (node (ref "LED45") (pin "5") (pinfunction "GND_5") (pintype "input"))
      (node (ref "LED46") (pin "5") (pinfunction "GND_5") (pintype "input"))
      (node (ref "LED47") (pin "5") (pinfunction "GND_5") (pintype "input"))
      (node (ref "LED48") (pin "5") (pinfunction "GND_5") (pintype "input"))
      (node (ref "LED49") (pin "5") (pinfunction "GND_5") (pintype "input"))
      (node (ref "LED5") (pin "5") (pinfunction "GND_5") (pintype "input"))
      (node (ref "LED50") (pin "5") (pinfunction "GND_5") (pintype "input"))
      (node (ref "LED51") (pin "5") (pinfunction "GND_5") (pintype "input"))
      (node (ref "LED52") (pin "5") (pinfunction "GND_5") (pintype "input"))
      (node (ref "LED53") (pin "5") (pinfunction "GND_5") (pintype "input"))
      (node (ref "LED54") (pin "5") (pinfunction "GND_5") (pintype "input"))
      (node (ref "LED55") (pin "5") (pinfunction "GND_5") (pintype "input"))
      (node (ref "LED56") (pin "5") (pinfunction "GND_5") (pintype "input"))
      (node (ref "LED57") (pin "5") (pinfunction "GND_5") (pintype "input"))
      (node (ref "LED58") (pin "5") (pinfunction "GND_5") (pintype "input"))
      (node (ref "LED59") (pin "5") (pinfunction "GND_5") (pintype "input"))
      (node (ref "LED6") (pin "5") (pinfunction "GND_5") (pintype "input"))
      (node (ref "LED60") (pin "5") (pinfunction "GND_5") (pintype "input"))
      (node (ref "LED61") (pin "5") (pinfunction "GND_5") (pintype "input"))
      (node (ref "LED62") (pin "5") (pinfunction "GND_5") (pintype "input"))
      (node (ref "LED63") (pin "5") (pinfunction "GND_5") (pintype "input"))
      (node (ref "LED7") (pin "5") (pinfunction "GND_5") (pintype "input"))
      (node (ref "LED8") (pin "5") (pinfunction "GND_5") (pintype "input"))
      (node (ref "LED9") (pin "5") (pinfunction "GND_5") (pintype "input"))
      (node (ref "U2") (pin "4") (pinfunction "GND_4") (pintype "input"))
    )
    (net (code "12") (name "Net-(LED1-BO)") (class "Default")
      (node (ref "LED1") (pin "1") (pinfunction "BO_1") (pintype "input"))
      (node (ref "LED2") (pin "6") (pinfunction "BI_6") (pintype "input"))
    )
    (net (code "13") (name "Net-(LED1-DO)") (class "Default")
      (node (ref "LED1") (pin "3") (pinfunction "DO_3") (pintype "input"))
      (node (ref "LED2") (pin "4") (pinfunction "DI_4") (pintype "input"))
    )
    (net (code "14") (name "Net-(LED2-BO)") (class "Default")
      (node (ref "LED2") (pin "1") (pinfunction "BO_1") (pintype "input"))
      (node (ref "LED3") (pin "6") (pinfunction "BI_6") (pintype "input"))
    )
    (net (code "15") (name "Net-(LED2-DO)") (class "Default")
      (node (ref "LED2") (pin "3") (pinfunction "DO_3") (pintype "input"))
      (node (ref "LED3") (pin "4") (pinfunction "DI_4") (pintype "input"))
    )
    (net (code "16") (name "Net-(LED3-BO)") (class "Default")
      (node (ref "LED3") (pin "1") (pinfunction "BO_1") (pintype "input"))
      (node (ref "LED4") (pin "6") (pinfunction "BI_6") (pintype "input"))
    )
    (net (code "17") (name "Net-(LED3-DO)") (class "Default")
      (node (ref "LED3") (pin "3") (pinfunction "DO_3") (pintype "input"))
      (node (ref "LED4") (pin "4") (pinfunction "DI_4") (pintype "input"))
    )
    (net (code "18") (name "Net-(LED4-BO)") (class "Default")
      (node (ref "LED4") (pin "1") (pinfunction "BO_1") (pintype "input"))
      (node (ref "LED5") (pin "6") (pinfunction "BI_6") (pintype "input"))
    )
    (net (code "19") (name "Net-(LED4-DO)") (class "Default")
      (node (ref "LED4") (pin "3") (pinfunction "DO_3") (pintype "input"))
      (node (ref "LED5") (pin "4") (pinfunction "DI_4") (pintype "input"))
    )
    (net (code "20") (name "Net-(LED5-BO)") (class "Default")
      (node (ref "LED5") (pin "1") (pinfunction "BO_1") (pintype "input"))
      (node (ref "LED6") (pin "6") (pinfunction "BI_6") (pintype "input"))
    )
    (net (code "21") (name "Net-(LED5-DO)") (class "Default")
      (node (ref "LED5") (pin "3") (pinfunction "DO_3") (pintype "input"))
      (node (ref "LED6") (pin "4") (pinfunction "DI_4") (pintype "input"))
    )
    (net (code "22") (name "Net-(LED6-BO)") (class "Default")
      (node (ref "LED6") (pin "1") (pinfunction "BO_1") (pintype "input"))
      (node (ref "LED7") (pin "6") (pinfunction "BI_6") (pintype "input"))
    )
    (net (code "23") (name "Net-(LED6-DO)") (class "Default")
      (node (ref "LED6") (pin "3") (pinfunction "DO_3") (pintype "input"))
      (node (ref "LED7") (pin "4") (pinfunction "DI_4") (pintype "input"))
    )
    (net (code "24") (name "Net-(LED7-BO)") (class "Default")
      (node (ref "LED7") (pin "1") (pinfunction "BO_1") (pintype "input"))
      (node (ref "LED8") (pin "6") (pinfunction "BI_6") (pintype "input"))
    )
    (net (code "25") (name "Net-(LED7-DO)") (class "Default")
      (node (ref "LED7") (pin "3") (pinfunction "DO_3") (pintype "input"))
      (node (ref "LED8") (pin "4") (pinfunction "DI_4") (pintype "input"))
    )
    (net (code "26") (name "Net-(LED8-BO)") (class "Default")
      (node (ref "LED8") (pin "1") (pinfunction "BO_1") (pintype "input"))
      (node (ref "LED9") (pin "6") (pinfunction "BI_6") (pintype "input"))
    )
    (net (code "27") (name "Net-(LED8-DO)") (class "Default")
      (node (ref "LED8") (pin "3") (pinfunction "DO_3") (pintype "input"))
      (node (ref "LED9") (pin "4") (pinfunction "DI_4") (pintype "input"))
    )
    (net (code "28") (name "Net-(LED10-BI)") (class "Default")
      (node (ref "LED10") (pin "6") (pinfunction "BI_6") (pintype "input"))
      (node (ref "LED9") (pin "1") (pinfunction "BO_1") (pintype "input"))
    )
    (net (code "29") (name "Net-(LED10-BO)") (class "Default")
      (node (ref "LED10") (pin "1") (pinfunction "BO_1") (pintype "input"))
      (node (ref "LED11") (pin "6") (pinfunction "BI_6") (pintype "input"))
    )
    (net (code "30") (name "Net-(LED10-DI)") (class "Default")
      (node (ref "LED10") (pin "4") (pinfunction "DI_4") (pintype "input"))
      (node (ref "LED9") (pin "3") (pinfunction "DO_3") (pintype "input"))
    )
    (net (code "31") (name "Net-(LED10-DO)") (class "Default")
      (node (ref "LED10") (pin "3") (pinfunction "DO_3") (pintype "input"))
      (node (ref "LED11") (pin "4") (pinfunction "DI_4") (pintype "input"))
    )
    (net (code "32") (name "Net-(LED11-BO)") (class "Default")
      (node (ref "LED11") (pin "1") (pinfunction "BO_1") (pintype "input"))
      (node (ref "LED12") (pin "6") (pinfunction "BI_6") (pintype "input"))
    )
    (net (code "33") (name "Net-(LED11-DO)") (class "Default")
      (node (ref "LED11") (pin "3") (pinfunction "DO_3") (pintype "input"))
      (node (ref "LED12") (pin "4") (pinfunction "DI_4") (pintype "input"))
    )
    (net (code "34") (name "Net-(LED12-BO)") (class "Default")
      (node (ref "LED12") (pin "1") (pinfunction "BO_1") (pintype "input"))
      (node (ref "LED13") (pin "6") (pinfunction "BI_6") (pintype "input"))
    )
    (net (code "35") (name "Net-(LED12-DO)") (class "Default")
      (node (ref "LED12") (pin "3") (pinfunction "DO_3") (pintype "input"))
      (node (ref "LED13") (pin "4") (pinfunction "DI_4") (pintype "input"))
    )
    (net (code "36") (name "Net-(LED13-BO)") (class "Default")
      (node (ref "LED13") (pin "1") (pinfunction "BO_1") (pintype "input"))
      (node (ref "LED14") (pin "6") (pinfunction "BI_6") (pintype "input"))
    )
    (net (code "37") (name "Net-(LED13-DO)") (class "Default")
      (node (ref "LED13") (pin "3") (pinfunction "DO_3") (pintype "input"))
      (node (ref "LED14") (pin "4") (pinfunction "DI_4") (pintype "input"))
    )
    (net (code "38") (name "Net-(LED14-BO)") (class "Default")
      (node (ref "LED14") (pin "1") (pinfunction "BO_1") (pintype "input"))
      (node (ref "LED15") (pin "6") (pinfunction "BI_6") (pintype "input"))
    )
    (net (code "39") (name "Net-(LED14-DO)") (class "Default")
      (node (ref "LED14") (pin "3") (pinfunction "DO_3") (pintype "input"))
      (node (ref "LED15") (pin "4") (pinfunction "DI_4") (pintype "input"))
    )
    (net (code "40") (name "Net-(LED15-BO)") (class "Default")
      (node (ref "LED15") (pin "1") (pinfunction "BO_1") (pintype "input"))
      (node (ref "LED16") (pin "6") (pinfunction "BI_6") (pintype "input"))
    )
    (net (code "41") (name "Net-(LED15-DO)") (class "Default")
      (node (ref "LED15") (pin "3") (pinfunction "DO_3") (pintype "input"))
      (node (ref "LED16") (pin "4") (pinfunction "DI_4") (pintype "input"))
    )
    (net (code "42") (name "Net-(LED16-BO)") (class "Default")
      (node (ref "LED16") (pin "1") (pinfunction "BO_1") (pintype "input"))
      (node (ref "LED17") (pin "6") (pinfunction "BI_6") (pintype "input"))
    )
    (net (code "43") (name "Net-(LED16-DO)") (class "Default")
      (node (ref "LED16") (pin "3") (pinfunction "DO_3") (pintype "input"))
      (node (ref "LED17") (pin "4") (pinfunction "DI_4") (pintype "input"))
    )
    (net (code "44") (name "Net-(LED17-BO)") (class "Default")
      (node (ref "LED17") (pin "1") (pinfunction "BO_1") (pintype "input"))
      (node (ref "LED18") (pin "6") (pinfunction "BI_6") (pintype "input"))
    )
    (net (code "45") (name "Net-(LED17-DO)") (class "Default")
      (node (ref "LED17") (pin "3") (pinfunction "DO_3") (pintype "input"))
      (node (ref "LED18") (pin "4") (pinfunction "DI_4") (pintype "input"))
    )
    (net (code "46") (name "Net-(LED18-BO)") (class "Default")
      (node (ref "LED18") (pin "1") (pinfunction "BO_1") (pintype "input"))
      (node (ref "LED19") (pin "6") (pinfunction "BI_6") (pintype "input"))
    )
    (net (code "47") (name "Net-(LED18-DO)") (class "Default")
      (node (ref "LED18") (pin "3") (pinfunction "DO_3") (pintype "input"))
      (node (ref "LED19") (pin "4") (pinfunction "DI_4") (pintype "input"))
    )
    (net (code "48") (name "Net-(LED19-BO)") (class "Default")
      (node (ref "LED19") (pin "1") (pinfunction "BO_1") (pintype "input"))
      (node (ref "LED20") (pin "6") (pinfunction "BI_6") (pintype "input"))
    )
    (net (code "49") (name "Net-(LED19-DO)") (class "Default")
      (node (ref "LED19") (pin "3") (pinfunction "DO_3") (pintype "input"))
      (node (ref "LED20") (pin "4") (pinfunction "DI_4") (pintype "input"))
    )
    (net (code "50") (name "Net-(LED20-BO)") (class "Default")
      (node (ref "LED20") (pin "1") (pinfunction "BO_1") (pintype "input"))
      (node (ref "LED21") (pin "6") (pinfunction "BI_6") (pintype "input"))
    )
    (net (code "51") (name "Net-(LED20-DO)") (class "Default")
      (node (ref "LED20") (pin "3") (pinfunction "DO_3") (pintype "input"))
      (node (ref "LED21") (pin "4") (pinfunction "DI_4") (pintype "input"))
    )
    (net (code "52") (name "Net-(LED22-BO)") (class "Default")
      (node (ref "LED22") (pin "1") (pinfunction "BO_1") (pintype "input"))
      (node (ref "LED23") (pin "6") (pinfunction "BI_6") (pintype "input"))
    )
    (net (code "53") (name "Net-(LED22-DO)") (class "Default")
      (node (ref "LED22") (pin "3") (pinfunction "DO_3") (pintype "input"))
      (node (ref "LED23") (pin "4") (pinfunction "DI_4") (pintype "input"))
    )
    (net (code "54") (name "Net-(LED23-BO)") (class "Default")
      (node (ref "LED23") (pin "1") (pinfunction "BO_1") (pintype "input"))
      (node (ref "LED24") (pin "6") (pinfunction "BI_6") (pintype "input"))
    )
    (net (code "55") (name "Net-(LED23-DO)") (class "Default")
      (node (ref "LED23") (pin "3") (pinfunction "DO_3") (pintype "input"))
      (node (ref "LED24") (pin "4") (pinfunction "DI_4") (pintype "input"))
    )
    (net (code "56") (name "Net-(LED24-BO)") (class "Default")
      (node (ref "LED24") (pin "1") (pinfunction "BO_1") (pintype "input"))
      (node (ref "LED25") (pin "6") (pinfunction "BI_6") (pintype "input"))
    )
    (net (code "57") (name "Net-(LED24-DO)") (class "Default")
      (node (ref "LED24") (pin "3") (pinfunction "DO_3") (pintype "input"))
      (node (ref "LED25") (pin "4") (pinfunction "DI_4") (pintype "input"))
    )
    (net (code "58") (name "Net-(LED25-BO)") (class "Default")
      (node (ref "LED25") (pin "1") (pinfunction "BO_1") (pintype "input"))
      (node (ref "LED26") (pin "6") (pinfunction "BI_6") (pintype "input"))
    )
    (net (code "59") (name "Net-(LED25-DO)") (class "Default")
      (node (ref "LED25") (pin "3") (pinfunction "DO_3") (pintype "input"))
      (node (ref "LED26") (pin "4") (pinfunction "DI_4") (pintype "input"))
    )
    (net (code "60") (name "Net-(LED26-BO)") (class "Default")
      (node (ref "LED26") (pin "1") (pinfunction "BO_1") (pintype "input"))
      (node (ref "LED27") (pin "6") (pinfunction "BI_6") (pintype "input"))
    )
    (net (code "61") (name "Net-(LED26-DO)") (class "Default")
      (node (ref "LED26") (pin "3") (pinfunction "DO_3") (pintype "input"))
      (node (ref "LED27") (pin "4") (pinfunction "DI_4") (pintype "input"))
    )
    (net (code "62") (name "Net-(LED27-BO)") (class "Default")
      (node (ref "LED27") (pin "1") (pinfunction "BO_1") (pintype "input"))
      (node (ref "LED28") (pin "6") (pinfunction "BI_6") (pintype "input"))
    )
    (net (code "63") (name "Net-(LED27-DO)") (class "Default")
      (node (ref "LED27") (pin "3") (pinfunction "DO_3") (pintype "input"))
      (node (ref "LED28") (pin "4") (pinfunction "DI_4") (pintype "input"))
    )
    (net (code "64") (name "Net-(LED28-BO)") (class "Default")
      (node (ref "LED28") (pin "1") (pinfunction "BO_1") (pintype "input"))
      (node (ref "LED29") (pin "6") (pinfunction "BI_6") (pintype "input"))
    )
    (net (code "65") (name "Net-(LED28-DO)") (class "Default")
      (node (ref "LED28") (pin "3") (pinfunction "DO_3") (pintype "input"))
      (node (ref "LED29") (pin "4") (pinfunction "DI_4") (pintype "input"))
    )
    (net (code "66") (name "Net-(LED29-BO)") (class "Default")
      (node (ref "LED29") (pin "1") (pinfunction "BO_1") (pintype "input"))
      (node (ref "LED30") (pin "6") (pinfunction "BI_6") (pintype "input"))
    )
    (net (code "67") (name "Net-(LED29-DO)") (class "Default")
      (node (ref "LED29") (pin "3") (pinfunction "DO_3") (pintype "input"))
      (node (ref "LED30") (pin "4") (pinfunction "DI_4") (pintype "input"))
    )
    (net (code "68") (name "Net-(LED30-BO)") (class "Default")
      (node (ref "LED30") (pin "1") (pinfunction "BO_1") (pintype "input"))
      (node (ref "LED31") (pin "6") (pinfunction "BI_6") (pintype "input"))
    )
    (net (code "69") (name "Net-(LED30-DO)") (class "Default")
      (node (ref "LED30") (pin "3") (pinfunction "DO_3") (pintype "input"))
      (node (ref "LED31") (pin "4") (pinfunction "DI_4") (pintype "input"))
    )
    (net (code "70") (name "Net-(LED31-BO)") (class "Default")
      (node (ref "LED31") (pin "1") (pinfunction "BO_1") (pintype "input"))
      (node (ref "LED32") (pin "6") (pinfunction "BI_6") (pintype "input"))
    )
    (net (code "71") (name "Net-(LED31-DO)") (class "Default")
      (node (ref "LED31") (pin "3") (pinfunction "DO_3") (pintype "input"))
      (node (ref "LED32") (pin "4") (pinfunction "DI_4") (pintype "input"))
    )
    (net (code "72") (name "Net-(LED32-BO)") (class "Default")
      (node (ref "LED32") (pin "1") (pinfunction "BO_1") (pintype "input"))
      (node (ref "LED33") (pin "6") (pinfunction "BI_6") (pintype "input"))
    )
    (net (code "73") (name "Net-(LED32-DO)") (class "Default")
      (node (ref "LED32") (pin "3") (pinfunction "DO_3") (pintype "input"))
      (node (ref "LED33") (pin "4") (pinfunction "DI_4") (pintype "input"))
    )
    (net (code "74") (name "Net-(LED33-BO)") (class "Default")
      (node (ref "LED33") (pin "1") (pinfunction "BO_1") (pintype "input"))
      (node (ref "LED34") (pin "6") (pinfunction "BI_6") (pintype "input"))
    )
    (net (code "75") (name "Net-(LED33-DO)") (class "Default")
      (node (ref "LED33") (pin "3") (pinfunction "DO_3") (pintype "input"))
      (node (ref "LED34") (pin "4") (pinfunction "DI_4") (pintype "input"))
    )
    (net (code "76") (name "Net-(LED34-BO)") (class "Default")
      (node (ref "LED34") (pin "1") (pinfunction "BO_1") (pintype "input"))
      (node (ref "LED35") (pin "6") (pinfunction "BI_6") (pintype "input"))
    )
    (net (code "77") (name "Net-(LED34-DO)") (class "Default")
      (node (ref "LED34") (pin "3") (pinfunction "DO_3") (pintype "input"))
      (node (ref "LED35") (pin "4") (pinfunction "DI_4") (pintype "input"))
    )
    (net (code "78") (name "Net-(LED35-BO)") (class "Default")
      (node (ref "LED35") (pin "1") (pinfunction "BO_1") (pintype "input"))
      (node (ref "LED36") (pin "6") (pinfunction "BI_6") (pintype "input"))
    )
    (net (code "79") (name "Net-(LED35-DO)") (class "Default")
      (node (ref "LED35") (pin "3") (pinfunction "DO_3") (pintype "input"))
      (node (ref "LED36") (pin "4") (pinfunction "DI_4") (pintype "input"))
    )
    (net (code "80") (name "Net-(LED36-BO)") (class "Default")
      (node (ref "LED36") (pin "1") (pinfunction "BO_1") (pintype "input"))
      (node (ref "LED37") (pin "6") (pinfunction "BI_6") (pintype "input"))
    )
    (net (code "81") (name "Net-(LED36-DO)") (class "Default")
      (node (ref "LED36") (pin "3") (pinfunction "DO_3") (pintype "input"))
      (node (ref "LED37") (pin "4") (pinfunction "DI_4") (pintype "input"))
    )
    (net (code "82") (name "Net-(LED37-BO)") (class "Default")
      (node (ref "LED37") (pin "1") (pinfunction "BO_1") (pintype "input"))
      (node (ref "LED38") (pin "6") (pinfunction "BI_6") (pintype "input"))
    )
    (net (code "83") (name "Net-(LED37-DO)") (class "Default")
      (node (ref "LED37") (pin "3") (pinfunction "DO_3") (pintype "input"))
      (node (ref "LED38") (pin "4") (pinfunction "DI_4") (pintype "input"))
    )
    (net (code "84") (name "Net-(LED38-BO)") (class "Default")
      (node (ref "LED38") (pin "1") (pinfunction "BO_1") (pintype "input"))
      (node (ref "LED39") (pin "6") (pinfunction "BI_6") (pintype "input"))
    )
    (net (code "85") (name "Net-(LED38-DO)") (class "Default")
      (node (ref "LED38") (pin "3") (pinfunction "DO_3") (pintype "input"))
      (node (ref "LED39") (pin "4") (pinfunction "DI_4") (pintype "input"))
    )
    (net (code "86") (name "Net-(LED39-BO)") (class "Default")
      (node (ref "LED39") (pin "1") (pinfunction "BO_1") (pintype "input"))
      (node (ref "LED40") (pin "6") (pinfunction "BI_6") (pintype "input"))
    )
    (net (code "87") (name "Net-(LED39-DO)") (class "Default")
      (node (ref "LED39") (pin "3") (pinfunction "DO_3") (pintype "input"))
      (node (ref "LED40") (pin "4") (pinfunction "DI_4") (pintype "input"))
    )
    (net (code "88") (name "Net-(LED40-BO)") (class "Default")
      (node (ref "LED40") (pin "1") (pinfunction "BO_1") (pintype "input"))
      (node (ref "LED41") (pin "6") (pinfunction "BI_6") (pintype "input"))
    )
    (net (code "89") (name "Net-(LED40-DO)") (class "Default")
      (node (ref "LED40") (pin "3") (pinfunction "DO_3") (pintype "input"))
      (node (ref "LED41") (pin "4") (pinfunction "DI_4") (pintype "input"))
    )
    (net (code "90") (name "Net-(LED41-BO)") (class "Default")
      (node (ref "LED41") (pin "1") (pinfunction "BO_1") (pintype "input"))
      (node (ref "LED42") (pin "6") (pinfunction "BI_6") (pintype "input"))
    )
    (net (code "91") (name "Net-(LED41-DO)") (class "Default")
      (node (ref "LED41") (pin "3") (pinfunction "DO_3") (pintype "input"))
      (node (ref "LED42") (pin "4") (pinfunction "DI_4") (pintype "input"))
    )
    (net (code "92") (name "Net-(LED43-BO)") (class "Default")
      (node (ref "LED43") (pin "1") (pinfunction "BO_1") (pintype "input"))
      (node (ref "LED44") (pin "6") (pinfunction "BI_6") (pintype "input"))
    )
    (net (code "93") (name "Net-(LED43-DO)") (class "Default")
      (node (ref "LED43") (pin "3") (pinfunction "DO_3") (pintype "input"))
      (node (ref "LED44") (pin "4") (pinfunction "DI_4") (pintype "input"))
    )
    (net (code "94") (name "Net-(LED44-BO)") (class "Default")
      (node (ref "LED44") (pin "1") (pinfunction "BO_1") (pintype "input"))
      (node (ref "LED45") (pin "6") (pinfunction "BI_6") (pintype "input"))
    )
    (net (code "95") (name "Net-(LED44-DO)") (class "Default")
      (node (ref "LED44") (pin "3") (pinfunction "DO_3") (pintype "input"))
      (node (ref "LED45") (pin "4") (pinfunction "DI_4") (pintype "input"))
    )
    (net (code "96") (name "Net-(LED45-BO)") (class "Default")
      (node (ref "LED45") (pin "1") (pinfunction "BO_1") (pintype "input"))
      (node (ref "LED46") (pin "6") (pinfunction "BI_6") (pintype "input"))
    )
    (net (code "97") (name "Net-(LED45-DO)") (class "Default")
      (node (ref "LED45") (pin "3") (pinfunction "DO_3") (pintype "input"))
      (node (ref "LED46") (pin "4") (pinfunction "DI_4") (pintype "input"))
    )
    (net (code "98") (name "Net-(LED46-BO)") (class "Default")
      (node (ref "LED46") (pin "1") (pinfunction "BO_1") (pintype "input"))
      (node (ref "LED47") (pin "6") (pinfunction "BI_6") (pintype "input"))
    )
    (net (code "99") (name "Net-(LED46-DO)") (class "Default")
      (node (ref "LED46") (pin "3") (pinfunction "DO_3") (pintype "input"))
      (node (ref "LED47") (pin "4") (pinfunction "DI_4") (pintype "input"))
    )
    (net (code "100") (name "Net-(LED47-BO)") (class "Default")
      (node (ref "LED47") (pin "1") (pinfunction "BO_1") (pintype "input"))
      (node (ref "LED48") (pin "6") (pinfunction "BI_6") (pintype "input"))
    )
    (net (code "101") (name "Net-(LED47-DO)") (class "Default")
      (node (ref "LED47") (pin "3") (pinfunction "DO_3") (pintype "input"))
      (node (ref "LED48") (pin "4") (pinfunction "DI_4") (pintype "input"))
    )
    (net (code "102") (name "Net-(LED48-BO)") (class "Default")
      (node (ref "LED48") (pin "1") (pinfunction "BO_1") (pintype "input"))
      (node (ref "LED49") (pin "6") (pinfunction "BI_6") (pintype "input"))
    )
    (net (code "103") (name "Net-(LED48-DO)") (class "Default")
      (node (ref "LED48") (pin "3") (pinfunction "DO_3") (pintype "input"))
      (node (ref "LED49") (pin "4") (pinfunction "DI_4") (pintype "input"))
    )
    (net (code "104") (name "Net-(LED49-BO)") (class "Default")
      (node (ref "LED49") (pin "1") (pinfunction "BO_1") (pintype "input"))
      (node (ref "LED50") (pin "6") (pinfunction "BI_6") (pintype "input"))
    )
    (net (code "105") (name "Net-(LED49-DO)") (class "Default")
      (node (ref "LED49") (pin "3") (pinfunction "DO_3") (pintype "input"))
      (node (ref "LED50") (pin "4") (pinfunction "DI_4") (pintype "input"))
    )
    (net (code "106") (name "Net-(LED50-BO)") (class "Default")
      (node (ref "LED50") (pin "1") (pinfunction "BO_1") (pintype "input"))
      (node (ref "LED51") (pin "6") (pinfunction "BI_6") (pintype "input"))
    )
    (net (code "107") (name "Net-(LED50-DO)") (class "Default")
      (node (ref "LED50") (pin "3") (pinfunction "DO_3") (pintype "input"))
      (node (ref "LED51") (pin "4") (pinfunction "DI_4") (pintype "input"))
    )
    (net (code "108") (name "Net-(LED51-BO)") (class "Default")
      (node (ref "LED51") (pin "1") (pinfunction "BO_1") (pintype "input"))
      (node (ref "LED52") (pin "6") (pinfunction "BI_6") (pintype "input"))
    )
    (net (code "109") (name "Net-(LED51-DO)") (class "Default")
      (node (ref "LED51") (pin "3") (pinfunction "DO_3") (pintype "input"))
      (node (ref "LED52") (pin "4") (pinfunction "DI_4") (pintype "input"))
    )
    (net (code "110") (name "Net-(LED52-BO)") (class "Default")
      (node (ref "LED52") (pin "1") (pinfunction "BO_1") (pintype "input"))
      (node (ref "LED53") (pin "6") (pinfunction "BI_6") (pintype "input"))
    )
    (net (code "111") (name "Net-(LED52-DO)") (class "Default")
      (node (ref "LED52") (pin "3") (pinfunction "DO_3") (pintype "input"))
      (node (ref "LED53") (pin "4") (pinfunction "DI_4") (pintype "input"))
    )
    (net (code "112") (name "Net-(LED53-BO)") (class "Default")
      (node (ref "LED53") (pin "1") (pinfunction "BO_1") (pintype "input"))
      (node (ref "LED54") (pin "6") (pinfunction "BI_6") (pintype "input"))
    )
    (net (code "113") (name "Net-(LED53-DO)") (class "Default")
      (node (ref "LED53") (pin "3") (pinfunction "DO_3") (pintype "input"))
      (node (ref "LED54") (pin "4") (pinfunction "DI_4") (pintype "input"))
    )
    (net (code "114") (name "Net-(LED54-BO)") (class "Default")
      (node (ref "LED54") (pin "1") (pinfunction "BO_1") (pintype "input"))
      (node (ref "LED55") (pin "6") (pinfunction "BI_6") (pintype "input"))
    )
    (net (code "115") (name "Net-(LED54-DO)") (class "Default")
      (node (ref "LED54") (pin "3") (pinfunction "DO_3") (pintype "input"))
      (node (ref "LED55") (pin "4") (pinfunction "DI_4") (pintype "input"))
    )
    (net (code "116") (name "Net-(LED55-BO)") (class "Default")
      (node (ref "LED55") (pin "1") (pinfunction "BO_1") (pintype "input"))
      (node (ref "LED56") (pin "6") (pinfunction "BI_6") (pintype "input"))
    )
    (net (code "117") (name "Net-(LED55-DO)") (class "Default")
      (node (ref "LED55") (pin "3") (pinfunction "DO_3") (pintype "input"))
      (node (ref "LED56") (pin "4") (pinfunction "DI_4") (pintype "input"))
    )
    (net (code "118") (name "Net-(LED56-BO)") (class "Default")
      (node (ref "LED56") (pin "1") (pinfunction "BO_1") (pintype "input"))
      (node (ref "LED57") (pin "6") (pinfunction "BI_6") (pintype "input"))
    )
    (net (code "119") (name "Net-(LED56-DO)") (class "Default")
      (node (ref "LED56") (pin "3") (pinfunction "DO_3") (pintype "input"))
      (node (ref "LED57") (pin "4") (pinfunction "DI_4") (pintype "input"))
    )
    (net (code "120") (name "Net-(LED57-BO)") (class "Default")
      (node (ref "LED57") (pin "1") (pinfunction "BO_1") (pintype "input"))
      (node (ref "LED58") (pin "6") (pinfunction "BI_6") (pintype "input"))
    )
    (net (code "121") (name "Net-(LED57-DO)") (class "Default")
      (node (ref "LED57") (pin "3") (pinfunction "DO_3") (pintype "input"))
      (node (ref "LED58") (pin "4") (pinfunction "DI_4") (pintype "input"))
    )
    (net (code "122") (name "Net-(LED58-BO)") (class "Default")
      (node (ref "LED58") (pin "1") (pinfunction "BO_1") (pintype "input"))
      (node (ref "LED59") (pin "6") (pinfunction "BI_6") (pintype "input"))
    )
    (net (code "123") (name "Net-(LED58-DO)") (class "Default")
      (node (ref "LED58") (pin "3") (pinfunction "DO_3") (pintype "input"))
      (node (ref "LED59") (pin "4") (pinfunction "DI_4") (pintype "input"))
    )
    (net (code "124") (name "Net-(LED59-BO)") (class "Default")
      (node (ref "LED59") (pin "1") (pinfunction "BO_1") (pintype "input"))
      (node (ref "LED60") (pin "6") (pinfunction "BI_6") (pintype "input"))
    )
    (net (code "125") (name "Net-(LED59-DO)") (class "Default")
      (node (ref "LED59") (pin "3") (pinfunction "DO_3") (pintype "input"))
      (node (ref "LED60") (pin "4") (pinfunction "DI_4") (pintype "input"))
    )
    (net (code "126") (name "Net-(LED60-BO)") (class "Default")
      (node (ref "LED60") (pin "1") (pinfunction "BO_1") (pintype "input"))
      (node (ref "LED61") (pin "6") (pinfunction "BI_6") (pintype "input"))
    )
    (net (code "127") (name "Net-(LED60-DO)") (class "Default")
      (node (ref "LED60") (pin "3") (pinfunction "DO_3") (pintype "input"))
      (node (ref "LED61") (pin "4") (pinfunction "DI_4") (pintype "input"))
    )
    (net (code "128") (name "Net-(LED61-BO)") (class "Default")
      (node (ref "LED61") (pin "1") (pinfunction "BO_1") (pintype "input"))
      (node (ref "LED62") (pin "6") (pinfunction "BI_6") (pintype "input"))
    )
    (net (code "129") (name "Net-(LED61-DO)") (class "Default")
      (node (ref "LED61") (pin "3") (pinfunction "DO_3") (pintype "input"))
      (node (ref "LED62") (pin "4") (pinfunction "DI_4") (pintype "input"))
    )
    (net (code "130") (name "Net-(LED62-BO)") (class "Default")
      (node (ref "LED62") (pin "1") (pinfunction "BO_1") (pintype "input"))
      (node (ref "LED63") (pin "6") (pinfunction "BI_6") (pintype "input"))
    )
    (net (code "131") (name "Net-(LED62-DO)") (class "Default")
      (node (ref "LED62") (pin "3") (pinfunction "DO_3") (pintype "input"))
      (node (ref "LED63") (pin "4") (pinfunction "DI_4") (pintype "input"))
    )
    (net (code "132") (name "Net-(U2-BST)") (class "Default")
      (node (ref "C2") (pin "1") (pinfunction "1_1") (pintype "unspecified"))
      (node (ref "U2") (pin "6") (pinfunction "BST_6") (pintype "input"))
    )
    (net (code "133") (name "Net-(U2-SW)") (class "Default")
      (node (ref "C2") (pin "2") (pinfunction "2_2") (pintype "unspecified"))
      (node (ref "L1") (pin "1") (pinfunction "1_1") (pintype "unspecified"))
      (node (ref "U2") (pin "5") (pinfunction "SW_5") (pintype "input"))
    )
    (net (code "134") (name "VCC") (class "Default")
      (node (ref "C1") (pin "1") (pinfunction "1_1") (pintype "input"))
      (node (ref "H1") (pin "11") (pinfunction "11_11") (pintype "unspecified"))
      (node (ref "H1") (pin "12") (pinfunction "12_12") (pintype "unspecified"))
      (node (ref "H2") (pin "11") (pinfunction "11_11") (pintype "unspecified"))
      (node (ref "H2") (pin "12") (pinfunction "12_12") (pintype "unspecified"))
      (node (ref "U2") (pin "3") (pinfunction "VIN_3") (pintype "input"))
    )
  )
)
